# 1-Power.net
KiCad netlist of a schematic drawn in Altium Designer
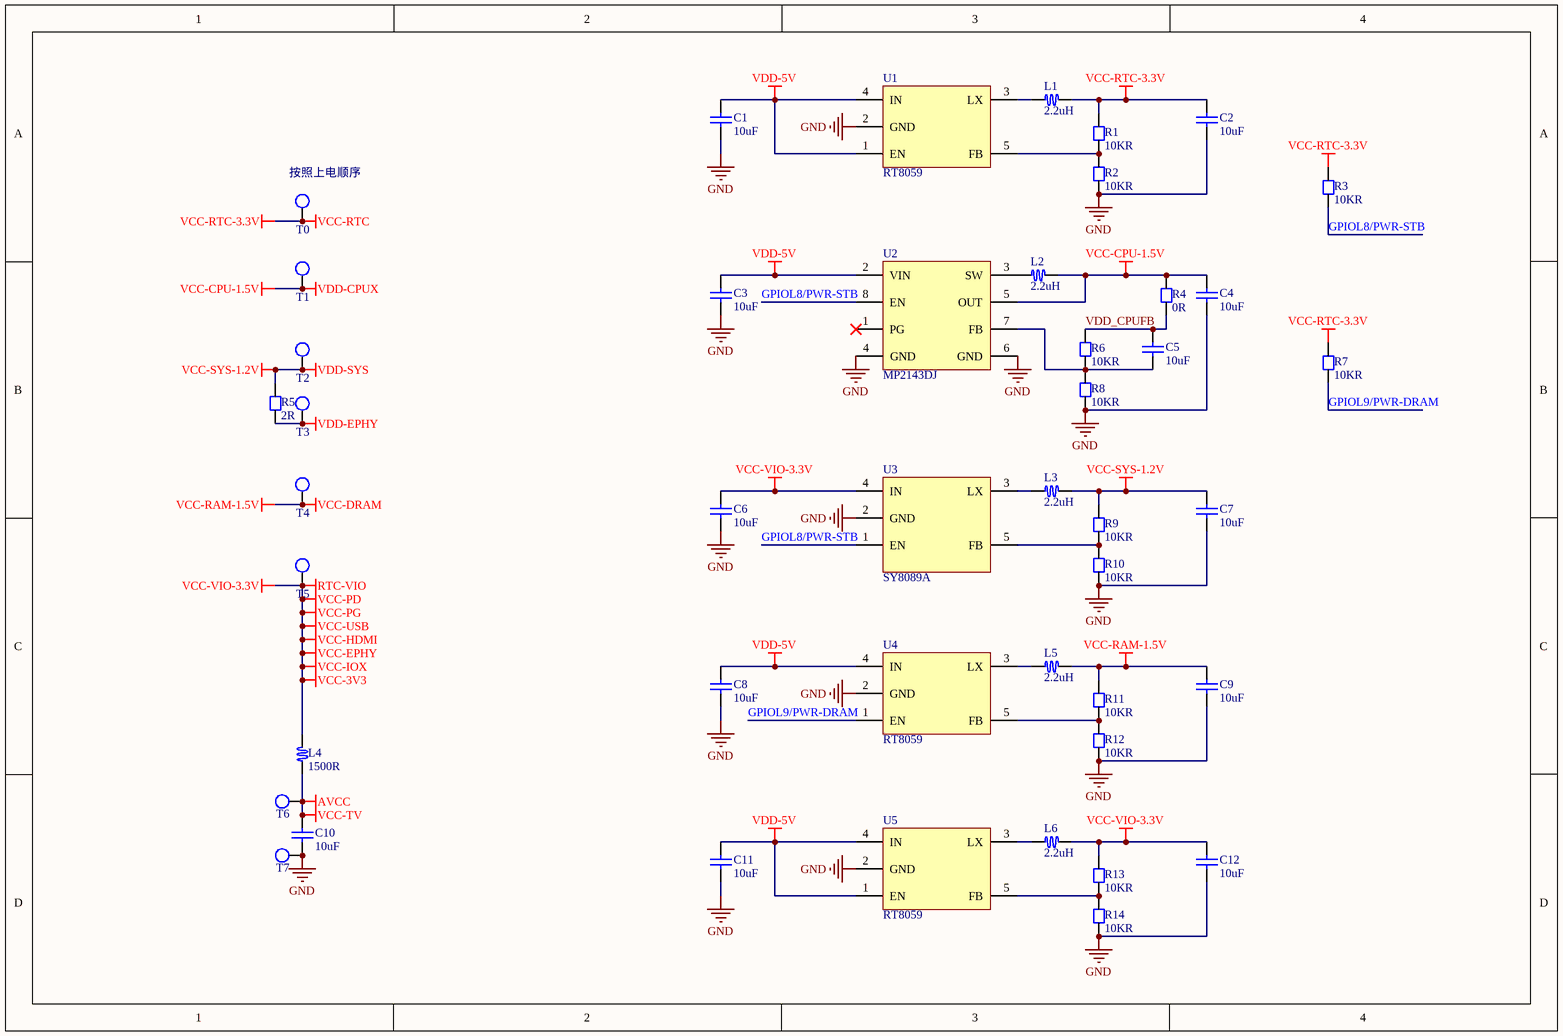
[diagram p0: 1-Power.SchDoc]

(export (version "E")
  (design (tool "Eeschema 10.0.6"))
  (components
    (comp (ref "C1")
      (value "10uF")
      (footprint "CC1005-0402")
      (description "贴片电容")
      (libsource (lib "tianxiaohua_Schlib") (part "Chip capacitor"))
    )
    (comp (ref "C2")
      (value "10uF")
      (footprint "CC1005-0402")
      (description "贴片电容")
      (libsource (lib "tianxiaohua_Schlib") (part "Chip capacitor"))
    )
    (comp (ref "C3")
      (value "10uF")
      (footprint "CC1005-0402")
      (description "贴片电容")
      (libsource (lib "tianxiaohua_Schlib") (part "Chip capacitor"))
    )
    (comp (ref "C4")
      (value "10uF")
      (footprint "CC1005-0402")
      (description "贴片电容")
      (libsource (lib "tianxiaohua_Schlib") (part "Chip capacitor"))
    )
    (comp (ref "C5")
      (value "10uF")
      (footprint "CC1005-0402")
      (description "贴片电容")
      (libsource (lib "tianxiaohua_Schlib") (part "Chip capacitor"))
    )
    (comp (ref "C6")
      (value "10uF")
      (footprint "CC1005-0402")
      (description "贴片电容")
      (libsource (lib "tianxiaohua_Schlib") (part "Chip capacitor"))
    )
    (comp (ref "C7")
      (value "10uF")
      (footprint "CC1005-0402")
      (description "贴片电容")
      (libsource (lib "tianxiaohua_Schlib") (part "Chip capacitor"))
    )
    (comp (ref "C8")
      (value "10uF")
      (footprint "CC1005-0402")
      (description "贴片电容")
      (libsource (lib "tianxiaohua_Schlib") (part "Chip capacitor"))
    )
    (comp (ref "C9")
      (value "10uF")
      (footprint "CC1005-0402")
      (description "贴片电容")
      (libsource (lib "tianxiaohua_Schlib") (part "Chip capacitor"))
    )
    (comp (ref "C10")
      (value "10uF")
      (footprint "CC1005-0402")
      (description "贴片电容")
      (libsource (lib "tianxiaohua_Schlib") (part "Chip capacitor"))
    )
    (comp (ref "C11")
      (value "10uF")
      (footprint "CC1005-0402")
      (description "贴片电容")
      (libsource (lib "tianxiaohua_Schlib") (part "Chip capacitor"))
    )
    (comp (ref "C12")
      (value "10uF")
      (footprint "CC1005-0402")
      (description "贴片电容")
      (libsource (lib "tianxiaohua_Schlib") (part "Chip capacitor"))
    )
    (comp (ref "L1")
      (value "2.2uH")
      (footprint "Inductor-3010")
      (description "贴片电感")
      (libsource (lib "tianxiaohua_Schlib") (part "Chip inductor"))
    )
    (comp (ref "L2")
      (value "2.2uH")
      (footprint "Inductor-4018")
      (description "贴片电感")
      (libsource (lib "tianxiaohua_Schlib") (part "Chip inductor"))
    )
    (comp (ref "L3")
      (value "2.2uH")
      (footprint "Inductor-3010")
      (description "贴片电感")
      (libsource (lib "tianxiaohua_Schlib") (part "Chip inductor"))
    )
    (comp (ref "L4")
      (value "1500R")
      (footprint "Inductor-0402")
      (description "贴片电感")
      (libsource (lib "") (part "Chip inductor_1"))
    )
    (comp (ref "L5")
      (value "2.2uH")
      (footprint "Inductor-3010")
      (description "贴片电感")
      (libsource (lib "tianxiaohua_Schlib") (part "Chip inductor"))
    )
    (comp (ref "L6")
      (value "2.2uH")
      (footprint "Inductor-3010")
      (description "贴片电感")
      (libsource (lib "tianxiaohua_Schlib") (part "Chip inductor"))
    )
    (comp (ref "R1")
      (value "10KR")
      (footprint "CR1005-0402")
      (description "贴片电阻")
      (libsource (lib "tianxiaohua_Schlib") (part "Chip resistor"))
    )
    (comp (ref "R2")
      (value "10KR")
      (footprint "CR1005-0402")
      (description "贴片电阻")
      (libsource (lib "tianxiaohua_Schlib") (part "Chip resistor"))
    )
    (comp (ref "R3")
      (value "10KR")
      (footprint "CR1005-0402")
      (description "贴片电阻")
      (libsource (lib "tianxiaohua_Schlib") (part "Chip resistor"))
    )
    (comp (ref "R4")
      (value "0R")
      (footprint "CR1005-0402")
      (description "贴片电阻")
      (libsource (lib "tianxiaohua_Schlib") (part "Chip resistor"))
    )
    (comp (ref "R5")
      (value "2R")
      (footprint "CR1005-0402")
      (description "贴片电阻")
      (libsource (lib "") (part "Chip resistor_1"))
    )
    (comp (ref "R6")
      (value "10KR")
      (footprint "CR1005-0402")
      (description "贴片电阻")
      (libsource (lib "tianxiaohua_Schlib") (part "Chip resistor"))
    )
    (comp (ref "R7")
      (value "10KR")
      (footprint "CR1005-0402")
      (description "贴片电阻")
      (libsource (lib "tianxiaohua_Schlib") (part "Chip resistor"))
    )
    (comp (ref "R8")
      (value "10KR")
      (footprint "CR1005-0402")
      (description "贴片电阻")
      (libsource (lib "tianxiaohua_Schlib") (part "Chip resistor"))
    )
    (comp (ref "R9")
      (value "10KR")
      (footprint "CR1005-0402")
      (description "贴片电阻")
      (libsource (lib "tianxiaohua_Schlib") (part "Chip resistor"))
    )
    (comp (ref "R10")
      (value "10KR")
      (footprint "CR1005-0402")
      (description "贴片电阻")
      (libsource (lib "tianxiaohua_Schlib") (part "Chip resistor"))
    )
    (comp (ref "R11")
      (value "10KR")
      (footprint "CR1005-0402")
      (description "贴片电阻")
      (libsource (lib "tianxiaohua_Schlib") (part "Chip resistor"))
    )
    (comp (ref "R12")
      (value "10KR")
      (footprint "CR1005-0402")
      (description "贴片电阻")
      (libsource (lib "tianxiaohua_Schlib") (part "Chip resistor"))
    )
    (comp (ref "R13")
      (value "10KR")
      (footprint "CR1005-0402")
      (description "贴片电阻")
      (libsource (lib "tianxiaohua_Schlib") (part "Chip resistor"))
    )
    (comp (ref "R14")
      (value "10KR")
      (footprint "CR1005-0402")
      (description "贴片电阻")
      (libsource (lib "tianxiaohua_Schlib") (part "Chip resistor"))
    )
    (comp (ref "T0")
      (value "Test")
      (footprint "TEST")
      (description "测试点")
      (libsource (lib "tianxiaohua_Schlib") (part "Test"))
    )
    (comp (ref "T1")
      (value "Test")
      (footprint "TEST")
      (description "测试点")
      (libsource (lib "tianxiaohua_Schlib") (part "Test"))
    )
    (comp (ref "T2")
      (value "Test")
      (footprint "TEST")
      (description "测试点")
      (libsource (lib "tianxiaohua_Schlib") (part "Test"))
    )
    (comp (ref "T3")
      (value "Test")
      (footprint "TEST")
      (description "测试点")
      (libsource (lib "tianxiaohua_Schlib") (part "Test"))
    )
    (comp (ref "T4")
      (value "Test")
      (footprint "TEST")
      (description "测试点")
      (libsource (lib "tianxiaohua_Schlib") (part "Test"))
    )
    (comp (ref "T5")
      (value "Test")
      (footprint "TEST")
      (description "测试点")
      (libsource (lib "tianxiaohua_Schlib") (part "Test"))
    )
    (comp (ref "T6")
      (value "Test")
      (footprint "TEST")
      (description "测试点")
      (libsource (lib "tianxiaohua_Schlib") (part "Test"))
    )
    (comp (ref "T7")
      (value "Test")
      (footprint "TEST")
      (description "测试点")
      (libsource (lib "tianxiaohua_Schlib") (part "Test"))
    )
    (comp (ref "U1")
      (value "RT8059")
      (footprint "SOT23-5")
      (description "LDO 1A RICHTEK(台湾立锜)")
      (libsource (lib "tianxiaohua_Schlib") (part "RT8059"))
    )
    (comp (ref "U2")
      (value "MP2143DJ")
      (footprint "TSOT23-8")
      (description "DCDC 3A MPS公司（中文名称：芯源信息系统有限公司）")
      (libsource (lib "tianxiaohua_Schlib") (part "MP2143DJ"))
    )
    (comp (ref "U3")
      (value "SY8089A")
      (footprint "SOT23-5")
      (description "DCDC 2A")
      (libsource (lib "tianxiaohua_Schlib") (part "SY8089A"))
    )
    (comp (ref "U4")
      (value "RT8059")
      (footprint "SOT23-5")
      (description "LDO 1A RICHTEK(台湾立锜)")
      (libsource (lib "tianxiaohua_Schlib") (part "RT8059"))
    )
    (comp (ref "U5")
      (value "RT8059")
      (footprint "SOT23-5")
      (description "LDO 1A RICHTEK(台湾立锜)")
      (libsource (lib "tianxiaohua_Schlib") (part "RT8059"))
    )
  )
  (nets
    (net (code "1") (name "/GPIOL8{slash}PWR-STB") (class "Default")
      (node (ref "R3") (pin "1") (pinfunction "1_1") (pintype "passive"))
      (node (ref "U2") (pin "8") (pinfunction "EN_8") (pintype "passive"))
      (node (ref "U3") (pin "1") (pinfunction "EN_1") (pintype "passive"))
    )
    (net (code "2") (name "/GPIOL9{slash}PWR-DRAM") (class "Default")
      (node (ref "R7") (pin "1") (pinfunction "1_1") (pintype "passive"))
      (node (ref "U4") (pin "1") (pinfunction "EN_1") (pintype "passive"))
    )
    (net (code "3") (name "/VDD_CPUFB") (class "Default")
      (node (ref "C5") (pin "2") (pinfunction "2_2") (pintype "passive"))
      (node (ref "R4") (pin "1") (pinfunction "1_1") (pintype "passive"))
      (node (ref "R6") (pin "2") (pinfunction "2_2") (pintype "passive"))
    )
    (net (code "4") (name "AVCC") (class "Default")
      (node (ref "C10") (pin "2") (pinfunction "2_2") (pintype "passive"))
      (node (ref "L4") (pin "1") (pinfunction "1_1") (pintype "passive"))
      (node (ref "T6") (pin "1") (pinfunction "1_1") (pintype "passive"))
    )
    (net (code "5") (name "GND") (class "Default")
      (node (ref "C1") (pin "1") (pinfunction "1_1") (pintype "passive"))
      (node (ref "C10") (pin "1") (pinfunction "1_1") (pintype "passive"))
      (node (ref "C11") (pin "1") (pinfunction "1_1") (pintype "passive"))
      (node (ref "C12") (pin "1") (pinfunction "1_1") (pintype "passive"))
      (node (ref "C2") (pin "1") (pinfunction "1_1") (pintype "passive"))
      (node (ref "C3") (pin "1") (pinfunction "1_1") (pintype "passive"))
      (node (ref "C4") (pin "1") (pinfunction "1_1") (pintype "passive"))
      (node (ref "C6") (pin "1") (pinfunction "1_1") (pintype "passive"))
      (node (ref "C7") (pin "1") (pinfunction "1_1") (pintype "passive"))
      (node (ref "C8") (pin "1") (pinfunction "1_1") (pintype "passive"))
      (node (ref "C9") (pin "1") (pinfunction "1_1") (pintype "passive"))
      (node (ref "R10") (pin "1") (pinfunction "1_1") (pintype "passive"))
      (node (ref "R12") (pin "1") (pinfunction "1_1") (pintype "passive"))
      (node (ref "R14") (pin "1") (pinfunction "1_1") (pintype "passive"))
      (node (ref "R2") (pin "1") (pinfunction "1_1") (pintype "passive"))
      (node (ref "R8") (pin "1") (pinfunction "1_1") (pintype "passive"))
      (node (ref "T7") (pin "1") (pinfunction "1_1") (pintype "passive"))
      (node (ref "U1") (pin "2") (pinfunction "GND_2") (pintype "passive"))
      (node (ref "U2") (pin "4") (pinfunction "GND_4") (pintype "passive"))
      (node (ref "U2") (pin "6") (pinfunction "GND_6") (pintype "passive"))
      (node (ref "U3") (pin "2") (pinfunction "GND_2") (pintype "passive"))
      (node (ref "U4") (pin "2") (pinfunction "GND_2") (pintype "passive"))
      (node (ref "U5") (pin "2") (pinfunction "GND_2") (pintype "passive"))
    )
    (net (code "6") (name "Net-(U1-FB)") (class "Default")
      (node (ref "R1") (pin "1") (pinfunction "1_1") (pintype "passive"))
      (node (ref "R2") (pin "2") (pinfunction "2_2") (pintype "passive"))
      (node (ref "U1") (pin "5") (pinfunction "FB_5") (pintype "passive"))
    )
    (net (code "7") (name "Net-(U1-LX)") (class "Default")
      (node (ref "L1") (pin "1") (pinfunction "1_1") (pintype "passive"))
      (node (ref "U1") (pin "3") (pinfunction "LX_3") (pintype "passive"))
    )
    (net (code "8") (name "Net-(U2-FB)") (class "Default")
      (node (ref "C5") (pin "1") (pinfunction "1_1") (pintype "passive"))
      (node (ref "R6") (pin "1") (pinfunction "1_1") (pintype "passive"))
      (node (ref "R8") (pin "2") (pinfunction "2_2") (pintype "passive"))
      (node (ref "U2") (pin "7") (pinfunction "FB_7") (pintype "passive"))
    )
    (net (code "9") (name "Net-(U2-SW)") (class "Default")
      (node (ref "L2") (pin "1") (pinfunction "1_1") (pintype "passive"))
      (node (ref "U2") (pin "3") (pinfunction "SW_3") (pintype "passive"))
    )
    (net (code "10") (name "Net-(U3-FB)") (class "Default")
      (node (ref "R10") (pin "2") (pinfunction "2_2") (pintype "passive"))
      (node (ref "R9") (pin "1") (pinfunction "1_1") (pintype "passive"))
      (node (ref "U3") (pin "5") (pinfunction "FB_5") (pintype "passive"))
    )
    (net (code "11") (name "Net-(U3-LX)") (class "Default")
      (node (ref "L3") (pin "1") (pinfunction "1_1") (pintype "passive"))
      (node (ref "U3") (pin "3") (pinfunction "LX_3") (pintype "passive"))
    )
    (net (code "12") (name "Net-(U4-FB)") (class "Default")
      (node (ref "R11") (pin "1") (pinfunction "1_1") (pintype "passive"))
      (node (ref "R12") (pin "2") (pinfunction "2_2") (pintype "passive"))
      (node (ref "U4") (pin "5") (pinfunction "FB_5") (pintype "passive"))
    )
    (net (code "13") (name "Net-(U4-LX)") (class "Default")
      (node (ref "L5") (pin "1") (pinfunction "1_1") (pintype "passive"))
      (node (ref "U4") (pin "3") (pinfunction "LX_3") (pintype "passive"))
    )
    (net (code "14") (name "Net-(U5-FB)") (class "Default")
      (node (ref "R13") (pin "1") (pinfunction "1_1") (pintype "passive"))
      (node (ref "R14") (pin "2") (pinfunction "2_2") (pintype "passive"))
      (node (ref "U5") (pin "5") (pinfunction "FB_5") (pintype "passive"))
    )
    (net (code "15") (name "Net-(U5-LX)") (class "Default")
      (node (ref "L6") (pin "1") (pinfunction "1_1") (pintype "passive"))
      (node (ref "U5") (pin "3") (pinfunction "LX_3") (pintype "passive"))
    )
    (net (code "16") (name "RTC-VIO") (class "Default")
      (node (ref "C12") (pin "2") (pinfunction "2_2") (pintype "passive"))
      (node (ref "C6") (pin "2") (pinfunction "2_2") (pintype "passive"))
      (node (ref "L4") (pin "2") (pinfunction "2_2") (pintype "passive"))
      (node (ref "L6") (pin "2") (pinfunction "2_2") (pintype "passive"))
      (node (ref "R13") (pin "2") (pinfunction "2_2") (pintype "passive"))
      (node (ref "T5") (pin "1") (pinfunction "1_1") (pintype "passive"))
      (node (ref "U3") (pin "4") (pinfunction "IN_4") (pintype "passive"))
    )
    (net (code "17") (name "VCC-CPU-1.5V") (class "Default")
      (node (ref "C4") (pin "2") (pinfunction "2_2") (pintype "passive"))
      (node (ref "L2") (pin "2") (pinfunction "2_2") (pintype "passive"))
      (node (ref "R4") (pin "2") (pinfunction "2_2") (pintype "passive"))
      (node (ref "T1") (pin "1") (pinfunction "1_1") (pintype "passive"))
      (node (ref "U2") (pin "5") (pinfunction "OUT_5") (pintype "passive"))
    )
    (net (code "18") (name "VCC-DRAM") (class "Default")
      (node (ref "C9") (pin "2") (pinfunction "2_2") (pintype "passive"))
      (node (ref "L5") (pin "2") (pinfunction "2_2") (pintype "passive"))
      (node (ref "R11") (pin "2") (pinfunction "2_2") (pintype "passive"))
      (node (ref "T4") (pin "1") (pinfunction "1_1") (pintype "passive"))
    )
    (net (code "19") (name "VCC-RTC") (class "Default")
      (node (ref "C2") (pin "2") (pinfunction "2_2") (pintype "passive"))
      (node (ref "L1") (pin "2") (pinfunction "2_2") (pintype "passive"))
      (node (ref "R1") (pin "2") (pinfunction "2_2") (pintype "passive"))
      (node (ref "R3") (pin "2") (pinfunction "2_2") (pintype "passive"))
      (node (ref "R7") (pin "2") (pinfunction "2_2") (pintype "passive"))
      (node (ref "T0") (pin "1") (pinfunction "1_1") (pintype "passive"))
    )
    (net (code "20") (name "VCC-SYS-1.2V") (class "Default")
      (node (ref "C7") (pin "2") (pinfunction "2_2") (pintype "passive"))
      (node (ref "L3") (pin "2") (pinfunction "2_2") (pintype "passive"))
      (node (ref "R5") (pin "1") (pinfunction "1_1") (pintype "passive"))
      (node (ref "R9") (pin "2") (pinfunction "2_2") (pintype "passive"))
      (node (ref "T2") (pin "1") (pinfunction "1_1") (pintype "passive"))
    )
    (net (code "21") (name "VDD-5V") (class "Default")
      (node (ref "C1") (pin "2") (pinfunction "2_2") (pintype "passive"))
      (node (ref "C11") (pin "2") (pinfunction "2_2") (pintype "passive"))
      (node (ref "C3") (pin "2") (pinfunction "2_2") (pintype "passive"))
      (node (ref "C8") (pin "2") (pinfunction "2_2") (pintype "passive"))
      (node (ref "U1") (pin "1") (pinfunction "EN_1") (pintype "passive"))
      (node (ref "U1") (pin "4") (pinfunction "IN_4") (pintype "passive"))
      (node (ref "U2") (pin "2") (pinfunction "VIN_2") (pintype "passive"))
      (node (ref "U4") (pin "4") (pinfunction "IN_4") (pintype "passive"))
      (node (ref "U5") (pin "1") (pinfunction "EN_1") (pintype "passive"))
      (node (ref "U5") (pin "4") (pinfunction "IN_4") (pintype "passive"))
    )
    (net (code "22") (name "VDD-EPHY") (class "Default")
      (node (ref "R5") (pin "2") (pinfunction "2_2") (pintype "passive"))
      (node (ref "T3") (pin "1") (pinfunction "1_1") (pintype "passive"))
    )
    (net (code "23") (name "unconnected-(U2-PG-Pad1)") (class "Default")
      (node (ref "U2") (pin "1") (pinfunction "PG_1") (pintype "passive+no_connect"))
    )
  )
)
